# mcu.net
KiCad netlist of a schematic drawn in Altium Designer
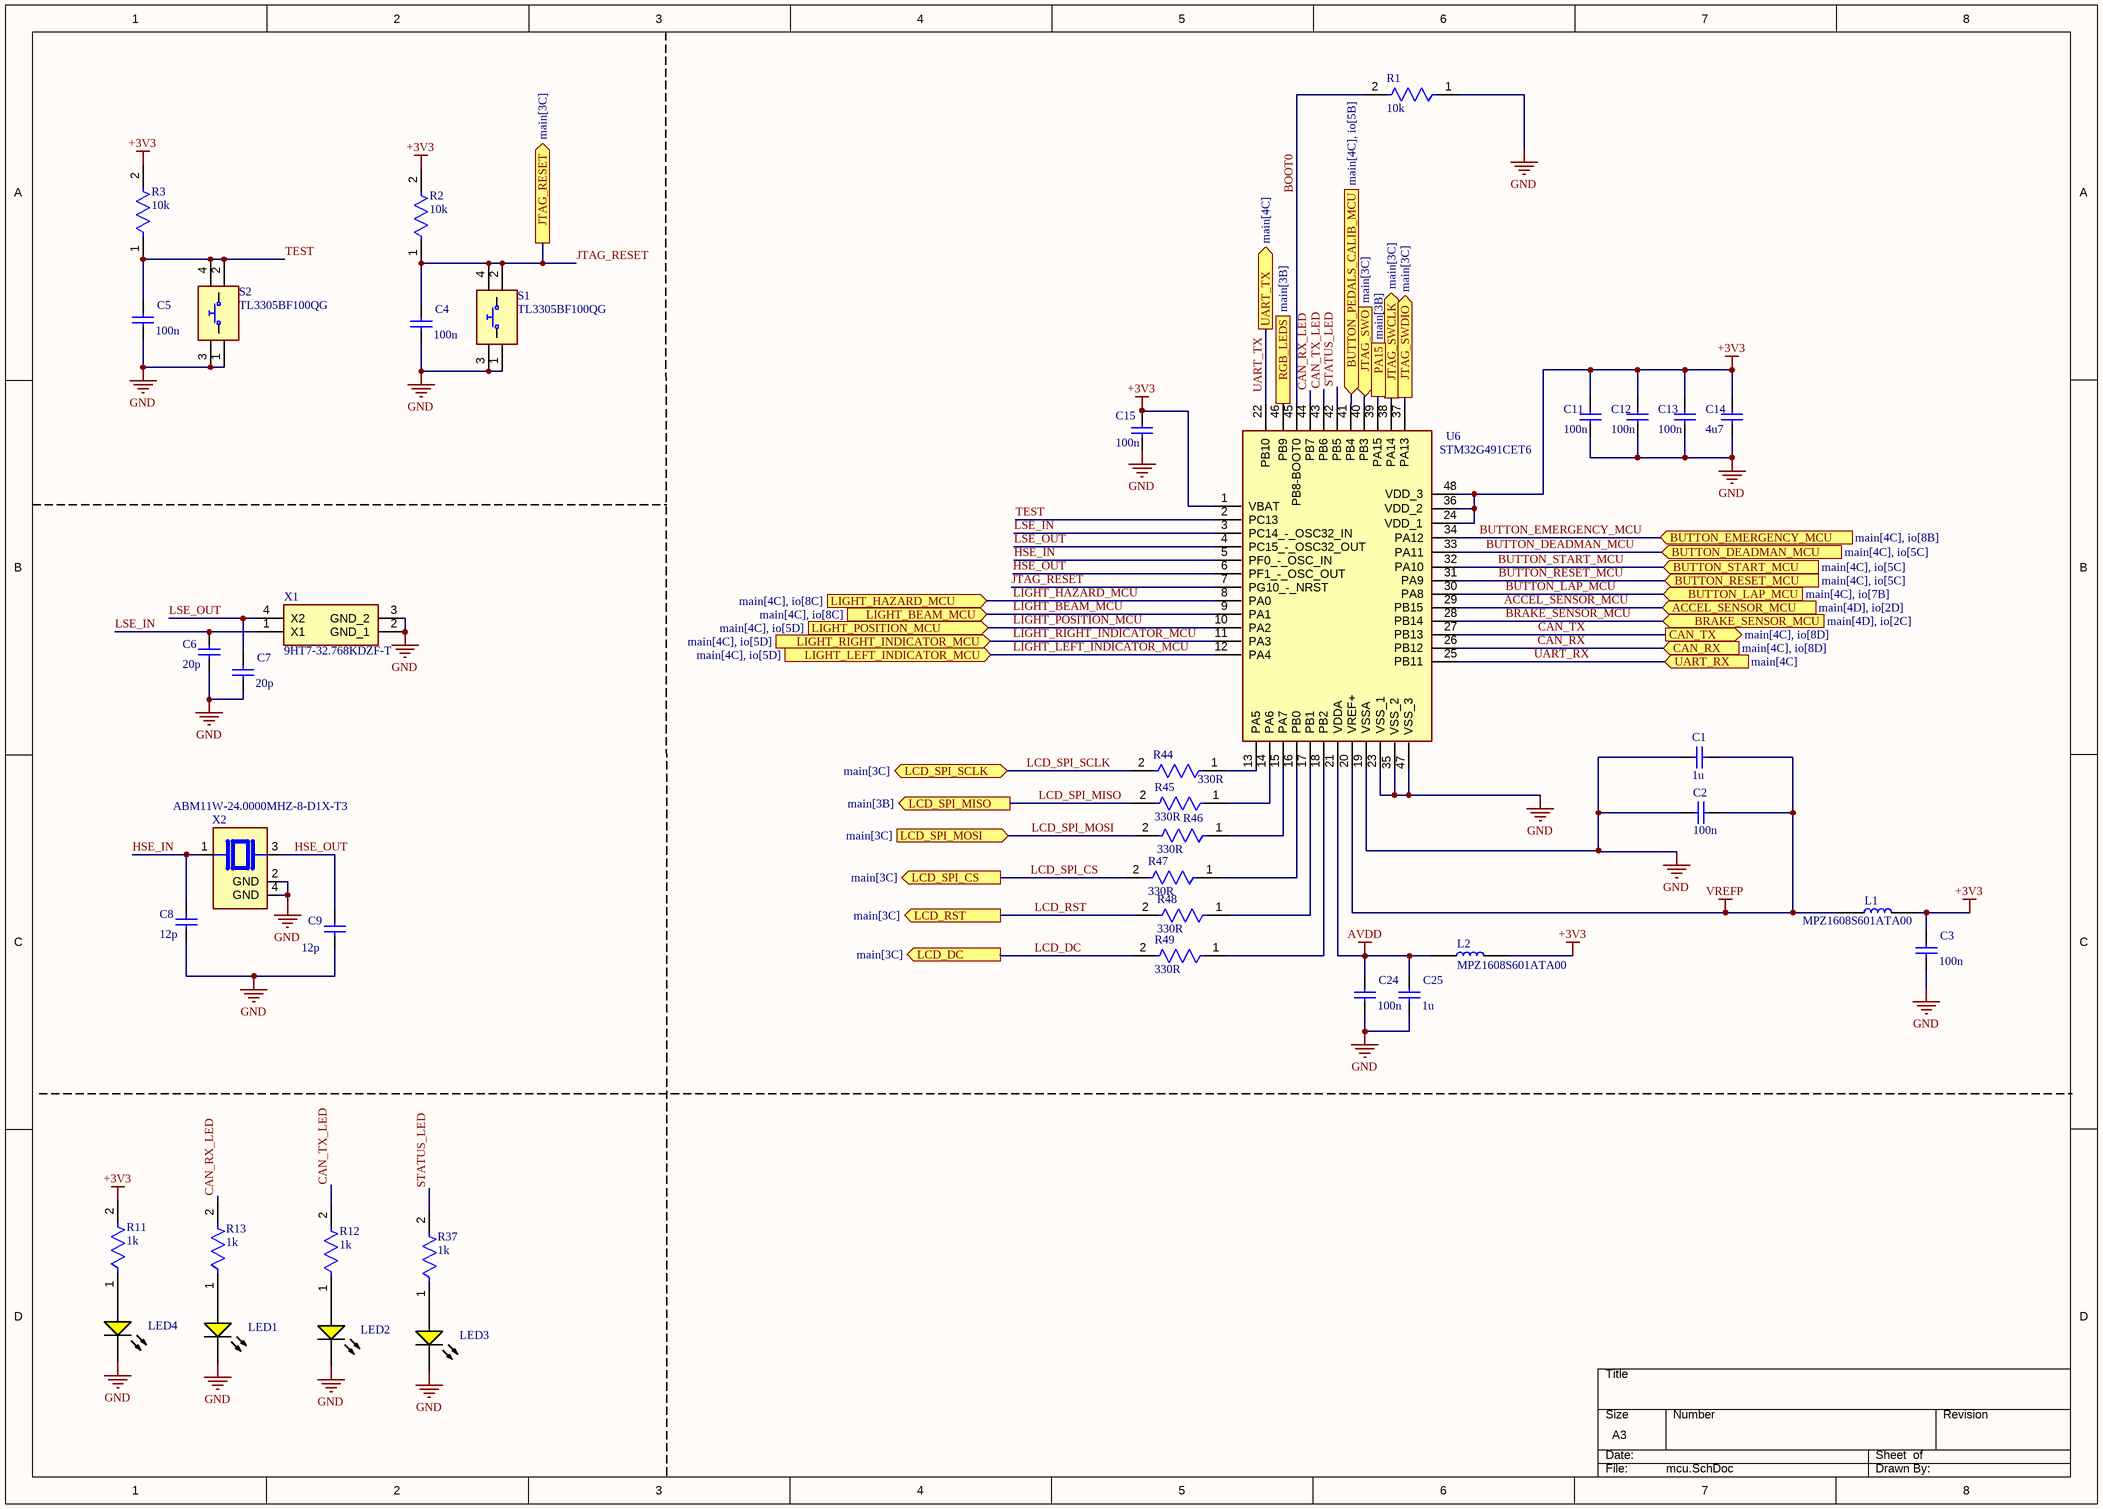
[diagram p0: mcu.SchDoc]

(export (version "E")
  (design (tool "Eeschema 10.0.6"))
  (components
    (comp (ref "C1")
      (value "1u")
      (footprint "CAPC1206(3216)150_L")
      (description "CAP 1.8uF 10V ±5% 1206 (3216 Metric) Thickness 1.45mm SMD")
      (fields (field (name "TOLERANCE") "Â±5%"))
      (libsource (lib "Altium Content Vault") (part "CAP"))
    )
    (comp (ref "C2")
      (value "100n")
      (footprint "CAPC1206(3216)150_L")
      (description "CAP 1.8uF 10V ±5% 1206 (3216 Metric) Thickness 1.45mm SMD")
      (fields (field (name "TOLERANCE") "Â±5%"))
      (libsource (lib "Altium Content Vault") (part "CAP"))
    )
    (comp (ref "C3")
      (value "100n")
      (footprint "CAPC1206(3216)150_L")
      (description "CAP 1.8uF 10V ±5% 1206 (3216 Metric) Thickness 1.45mm SMD")
      (fields (field (name "TOLERANCE") "Â±5%"))
      (libsource (lib "Altium Content Vault") (part "CAP"))
    )
    (comp (ref "C4")
      (value "100n")
      (footprint "CAPC1206(3216)150_L")
      (description "CAP 1.8uF 10V ±5% 1206 (3216 Metric) Thickness 1.45mm SMD")
      (fields (field (name "TOLERANCE") "Â±5%"))
      (libsource (lib "Altium Content Vault") (part "CAP"))
    )
    (comp (ref "C5")
      (value "100n")
      (footprint "CAPC1206(3216)150_L")
      (description "CAP 1.8uF 10V ±5% 1206 (3216 Metric) Thickness 1.45mm SMD")
      (fields (field (name "TOLERANCE") "Â±5%"))
      (libsource (lib "Altium Content Vault") (part "CAP"))
    )
    (comp (ref "C6")
      (value "20p")
      (footprint "CAPC1206(3216)150_L")
      (description "CAP 1.8uF 10V ±5% 1206 (3216 Metric) Thickness 1.45mm SMD")
      (fields (field (name "TOLERANCE") "Â±5%"))
      (libsource (lib "Altium Content Vault") (part "CAP"))
    )
    (comp (ref "C7")
      (value "20p")
      (footprint "CAPC1206(3216)150_L")
      (description "CAP 1.8uF 10V ±5% 1206 (3216 Metric) Thickness 1.45mm SMD")
      (fields (field (name "TOLERANCE") "Â±5%"))
      (libsource (lib "Altium Content Vault") (part "CAP"))
    )
    (comp (ref "C8")
      (value "12p")
      (footprint "CAPC1206(3216)150_L")
      (description "CAP 1.8uF 10V ±5% 1206 (3216 Metric) Thickness 1.45mm SMD")
      (fields (field (name "TOLERANCE") "Â±5%"))
      (libsource (lib "Altium Content Vault") (part "CAP"))
    )
    (comp (ref "C9")
      (value "12p")
      (footprint "CAPC1206(3216)150_L")
      (description "CAP 1.8uF 10V ±5% 1206 (3216 Metric) Thickness 1.45mm SMD")
      (fields (field (name "TOLERANCE") "Â±5%"))
      (libsource (lib "Altium Content Vault") (part "CAP"))
    )
    (comp (ref "C11")
      (value "100n")
      (footprint "CAPC1206(3216)150_L")
      (description "CAP 1.8uF 10V ±5% 1206 (3216 Metric) Thickness 1.45mm SMD")
      (fields (field (name "TOLERANCE") "Â±5%"))
      (libsource (lib "Altium Content Vault") (part "CAP"))
    )
    (comp (ref "C12")
      (value "100n")
      (footprint "CAPC1206(3216)150_L")
      (description "CAP 1.8uF 10V ±5% 1206 (3216 Metric) Thickness 1.45mm SMD")
      (fields (field (name "TOLERANCE") "Â±5%"))
      (libsource (lib "Altium Content Vault") (part "CAP"))
    )
    (comp (ref "C13")
      (value "100n")
      (footprint "CAPC1206(3216)150_L")
      (description "CAP 1.8uF 10V ±5% 1206 (3216 Metric) Thickness 1.45mm SMD")
      (fields (field (name "TOLERANCE") "Â±5%"))
      (libsource (lib "Altium Content Vault") (part "CAP"))
    )
    (comp (ref "C14")
      (value "4u7")
      (footprint "CAPC1206(3216)150_L")
      (description "CAP 1.8uF 10V ±5% 1206 (3216 Metric) Thickness 1.45mm SMD")
      (fields (field (name "TOLERANCE") "Â±5%"))
      (libsource (lib "Altium Content Vault") (part "CAP"))
    )
    (comp (ref "C15")
      (value "100n")
      (footprint "CAPC1206(3216)150_L")
      (description "CAP 1.8uF 10V ±5% 1206 (3216 Metric) Thickness 1.45mm SMD")
      (fields (field (name "TOLERANCE") "Â±5%"))
      (libsource (lib "Altium Content Vault") (part "CAP"))
    )
    (comp (ref "C24")
      (value "100n")
      (footprint "CAPC1206(3216)150_L")
      (description "CAP 1.8uF 10V ±5% 1206 (3216 Metric) Thickness 1.45mm SMD")
      (fields (field (name "TOLERANCE") "Â±5%"))
      (libsource (lib "Altium Content Vault") (part "CAP"))
    )
    (comp (ref "C25")
      (value "1u")
      (footprint "CAPC1206(3216)150_L")
      (description "CAP 1.8uF 10V ±5% 1206 (3216 Metric) Thickness 1.45mm SMD")
      (fields (field (name "TOLERANCE") "Â±5%"))
      (libsource (lib "Altium Content Vault") (part "CAP"))
    )
    (comp (ref "L1")
      (value "MPZ1608S601ATA00")
      (footprint "INDC1608X95N")
      (description "Ferrite Beads Multi-Layer 600Ohm 25% 100MHz 1A 0.15Ohm DCR 0603 T/R")
      (fields (field (name "MF") "TDK") (field (name "TOLERANCE") "25%"))
      (libsource (lib "HydrogreenLibrary") (part "MPZ1608S601ATA00"))
    )
    (comp (ref "L2")
      (value "MPZ1608S601ATA00")
      (footprint "INDC1608X95N")
      (description "Ferrite Beads Multi-Layer 600Ohm 25% 100MHz 1A 0.15Ohm DCR 0603 T/R")
      (fields (field (name "MF") "TDK") (field (name "TOLERANCE") "25%"))
      (libsource (lib "HydrogreenLibrary") (part "MPZ1608S601ATA00"))
    )
    (comp (ref "LED1")
      (value "~")
      (footprint "LUMX-SML-LX1206YC-TR_V")
      (description "Yellow LED, Water Clear Len, 585 nm, 2.1 V, -40 to 85 degC, 2-Pin SMD, RoHS, Tape and Reel")
      (fields (field (name "MANUFACTURER") "Lumex"))
      (libsource (lib "Altium Content Vault") (part "LED-YELLOW-AK-2"))
    )
    (comp (ref "LED2")
      (value "~")
      (footprint "LUMX-SML-LX1206YC-TR_V")
      (description "Yellow LED, Water Clear Len, 585 nm, 2.1 V, -40 to 85 degC, 2-Pin SMD, RoHS, Tape and Reel")
      (fields (field (name "MANUFACTURER") "Lumex"))
      (libsource (lib "Altium Content Vault") (part "LED-YELLOW-AK-2"))
    )
    (comp (ref "LED3")
      (value "~")
      (footprint "LUMX-SML-LX1206YC-TR_V")
      (description "Yellow LED, Water Clear Len, 585 nm, 2.1 V, -40 to 85 degC, 2-Pin SMD, RoHS, Tape and Reel")
      (fields (field (name "MANUFACTURER") "Lumex"))
      (libsource (lib "Altium Content Vault") (part "LED-YELLOW-AK-2"))
    )
    (comp (ref "LED4")
      (value "~")
      (footprint "LUMX-SML-LX1206YC-TR_V")
      (description "Yellow LED, Water Clear Len, 585 nm, 2.1 V, -40 to 85 degC, 2-Pin SMD, RoHS, Tape and Reel")
      (fields (field (name "MANUFACTURER") "Lumex"))
      (libsource (lib "Altium Content Vault") (part "LED-YELLOW-AK-2"))
    )
    (comp (ref "R1")
      (value "10k")
      (footprint "FP-RK73H2B-MFG")
      (description "40.2kΩ ±1% 0.25W Chip Resistor 1206 Thick Film AEC-Q200 Qualified")
      (fields (field (name "TOLERANCE") "1%"))
      (libsource (lib "Altium Content Vault") (part "1029c3af85768c4190bb7ad29bc67b5"))
    )
    (comp (ref "R2")
      (value "10k")
      (footprint "FP-RK73H2B-MFG")
      (description "40.2kΩ ±1% 0.25W Chip Resistor 1206 Thick Film AEC-Q200 Qualified")
      (fields (field (name "TOLERANCE") "1%"))
      (libsource (lib "Altium Content Vault") (part "1029c3af85768c4190bb7ad29bc67b5"))
    )
    (comp (ref "R3")
      (value "10k")
      (footprint "FP-RK73H2B-MFG")
      (description "40.2kΩ ±1% 0.25W Chip Resistor 1206 Thick Film AEC-Q200 Qualified")
      (fields (field (name "TOLERANCE") "1%"))
      (libsource (lib "Altium Content Vault") (part "1029c3af85768c4190bb7ad29bc67b5"))
    )
    (comp (ref "R11")
      (value "1k")
      (footprint "FP-RK73H2B-MFG")
      (description "40.2kΩ ±1% 0.25W Chip Resistor 1206 Thick Film AEC-Q200 Qualified")
      (fields (field (name "TOLERANCE") "1%"))
      (libsource (lib "Altium Content Vault") (part "1029c3af85768c4190bb7ad29bc67b5"))
    )
    (comp (ref "R12")
      (value "1k")
      (footprint "FP-RK73H2B-MFG")
      (description "40.2kΩ ±1% 0.25W Chip Resistor 1206 Thick Film AEC-Q200 Qualified")
      (fields (field (name "TOLERANCE") "1%"))
      (libsource (lib "Altium Content Vault") (part "1029c3af85768c4190bb7ad29bc67b5"))
    )
    (comp (ref "R13")
      (value "1k")
      (footprint "FP-RK73H2B-MFG")
      (description "40.2kΩ ±1% 0.25W Chip Resistor 1206 Thick Film AEC-Q200 Qualified")
      (fields (field (name "TOLERANCE") "1%"))
      (libsource (lib "Altium Content Vault") (part "1029c3af85768c4190bb7ad29bc67b5"))
    )
    (comp (ref "R37")
      (value "1k")
      (footprint "FP-RK73H2B-MFG")
      (description "40.2kΩ ±1% 0.25W Chip Resistor 1206 Thick Film AEC-Q200 Qualified")
      (fields (field (name "TOLERANCE") "1%"))
      (libsource (lib "Altium Content Vault") (part "1029c3af85768c4190bb7ad29bc67b5"))
    )
    (comp (ref "R44")
      (value "330R")
      (footprint "FP-RK73H2B-MFG")
      (description "40.2kΩ ±1% 0.25W Chip Resistor 1206 Thick Film AEC-Q200 Qualified")
      (fields (field (name "TOLERANCE") "1%"))
      (libsource (lib "Altium Content Vault") (part "1029c3af85768c4190bb7ad29bc67b5"))
    )
    (comp (ref "R45")
      (value "330R")
      (footprint "FP-RK73H2B-MFG")
      (description "40.2kΩ ±1% 0.25W Chip Resistor 1206 Thick Film AEC-Q200 Qualified")
      (fields (field (name "TOLERANCE") "1%"))
      (libsource (lib "Altium Content Vault") (part "1029c3af85768c4190bb7ad29bc67b5"))
    )
    (comp (ref "R46")
      (value "330R")
      (footprint "FP-RK73H2B-MFG")
      (description "40.2kΩ ±1% 0.25W Chip Resistor 1206 Thick Film AEC-Q200 Qualified")
      (fields (field (name "TOLERANCE") "1%"))
      (libsource (lib "Altium Content Vault") (part "1029c3af85768c4190bb7ad29bc67b5"))
    )
    (comp (ref "R47")
      (value "330R")
      (footprint "FP-RK73H2B-MFG")
      (description "40.2kΩ ±1% 0.25W Chip Resistor 1206 Thick Film AEC-Q200 Qualified")
      (fields (field (name "TOLERANCE") "1%"))
      (libsource (lib "Altium Content Vault") (part "1029c3af85768c4190bb7ad29bc67b5"))
    )
    (comp (ref "R48")
      (value "330R")
      (footprint "FP-RK73H2B-MFG")
      (description "40.2kΩ ±1% 0.25W Chip Resistor 1206 Thick Film AEC-Q200 Qualified")
      (fields (field (name "TOLERANCE") "1%"))
      (libsource (lib "Altium Content Vault") (part "1029c3af85768c4190bb7ad29bc67b5"))
    )
    (comp (ref "R49")
      (value "330R")
      (footprint "FP-RK73H2B-MFG")
      (description "40.2kΩ ±1% 0.25W Chip Resistor 1206 Thick Film AEC-Q200 Qualified")
      (fields (field (name "TOLERANCE") "1%"))
      (libsource (lib "Altium Content Vault") (part "1029c3af85768c4190bb7ad29bc67b5"))
    )
    (comp (ref "S1")
      (value "TL3305BF100QG")
      (footprint "TL3305BF160QG")
      (description "TL3305 Ultra-Miniature Tact Switch 100gf 5.0mm actuator Silver Contact Gullwing")
      (fields
        (field (name "MOUSER PART NUMBER") "612-TL3305BF100QG")
        (field (name "MANUFACTURER") "E-Switch")
      )
      (libsource (lib "HydrogreenLibrary") (part "TL3305BF100QG"))
    )
    (comp (ref "S2")
      (value "TL3305BF100QG")
      (footprint "TL3305BF160QG")
      (description "TL3305 Ultra-Miniature Tact Switch 100gf 5.0mm actuator Silver Contact Gullwing")
      (fields
        (field (name "MOUSER PART NUMBER") "612-TL3305BF100QG")
        (field (name "MANUFACTURER") "E-Switch")
      )
      (libsource (lib "HydrogreenLibrary") (part "TL3305BF100QG"))
    )
    (comp (ref "U6")
      (value "STM32G491CET6")
      (footprint "STM32G491CET6")
      (description "ARM Microcontrollers - MCU Mainstream Arm Cortex-M4+ MCU 170MHz with 512Kbytes of Flash memory")
      (fields (field (name "MOUSER PART NUMBER") "511-STM32G491CET6"))
      (libsource (lib "HydrogreenLibrary") (part "STM32G491CET6"))
    )
    (comp (ref "X1")
      (value "9HT7-32.768KDZF-T")
      (footprint "9HT732768KDZFT")
      (description "Parallel - Fundamental Quartz Crystal, 0.032768MHz Nom")
      (fields (field (name "MOUSER PART NUMBER") "717-9HT7-32.768KDZFT") (field (name "MANUFACTURER") "TXC"))
      (libsource (lib "HydrogreenLibrary") (part "9HT7-32.768KDZF-T"))
    )
    (comp (ref "X2")
      (value "ABM11W-24.0000MHZ-8-D1X-T3")
      (footprint "XTAL_ABM11W-24.0000MHZ-8-D1X-T3")
      (description "Crystal, Quartz, 24 MHz, SMD, 2mm x 1.6mm x 0.5mm, 20 ppm, 8 pF, 10 ppm, ABM11W")
      (fields (field (name "MF") "Abracon LLC") (field (name "MANUFACTURER") "Abracon"))
      (libsource (lib "HydrogreenLibrary") (part "ABM11W-24.0000MHZ-8-D1X-T3"))
    )
  )
  (nets
    (net (code "1") (name "+3V3") (class "Default")
      (node (ref "C11") (pin "1") (pinfunction "1_1") (pintype "passive"))
      (node (ref "C12") (pin "1") (pinfunction "1_1") (pintype "passive"))
      (node (ref "C13") (pin "1") (pinfunction "1_1") (pintype "passive"))
      (node (ref "C14") (pin "1") (pinfunction "1_1") (pintype "passive"))
      (node (ref "C15") (pin "1") (pinfunction "1_1") (pintype "passive"))
      (node (ref "C3") (pin "1") (pinfunction "1_1") (pintype "passive"))
      (node (ref "L1") (pin "2") (pinfunction "2_2") (pintype "passive"))
      (node (ref "L2") (pin "2") (pinfunction "2_2") (pintype "passive"))
      (node (ref "R11") (pin "2") (pinfunction "2_2") (pintype "passive"))
      (node (ref "R2") (pin "2") (pinfunction "2_2") (pintype "passive"))
      (node (ref "R3") (pin "2") (pinfunction "2_2") (pintype "passive"))
      (node (ref "U6") (pin "1") (pinfunction "VBAT_1") (pintype "passive"))
      (node (ref "U6") (pin "24") (pinfunction "VDD_1_24") (pintype "passive"))
      (node (ref "U6") (pin "36") (pinfunction "VDD_2_36") (pintype "passive"))
      (node (ref "U6") (pin "48") (pinfunction "VDD_3_48") (pintype "passive"))
    )
    (net (code "2") (name "/ACCEL_SENSOR_MCU") (class "Default")
      (node (ref "U6") (pin "29") (pinfunction "PB15_29") (pintype "passive"))
    )
    (net (code "3") (name "/BOOT0") (class "Default")
      (node (ref "R1") (pin "2") (pinfunction "2_2") (pintype "passive"))
      (node (ref "U6") (pin "45") (pinfunction "PB8-BOOT0_45") (pintype "passive"))
    )
    (net (code "4") (name "/BRAKE_SENSOR_MCU") (class "Default")
      (node (ref "U6") (pin "28") (pinfunction "PB14_28") (pintype "passive"))
    )
    (net (code "5") (name "/BUTTON_DEADMAN_MCU") (class "Default")
      (node (ref "U6") (pin "33") (pinfunction "PA11_33") (pintype "passive"))
    )
    (net (code "6") (name "/BUTTON_EMERGENCY_MCU") (class "Default")
      (node (ref "U6") (pin "34") (pinfunction "PA12_34") (pintype "passive"))
    )
    (net (code "7") (name "/BUTTON_LAP_MCU") (class "Default")
      (node (ref "U6") (pin "30") (pinfunction "PA8_30") (pintype "passive"))
    )
    (net (code "8") (name "/BUTTON_PEDALS_CALIB_MCU") (class "Default")
      (node (ref "U6") (pin "41") (pinfunction "PB4_41") (pintype "passive"))
    )
    (net (code "9") (name "/BUTTON_RESET_MCU") (class "Default")
      (node (ref "U6") (pin "31") (pinfunction "PA9_31") (pintype "passive"))
    )
    (net (code "10") (name "/BUTTON_START_MCU") (class "Default")
      (node (ref "U6") (pin "32") (pinfunction "PA10_32") (pintype "passive"))
    )
    (net (code "11") (name "/CAN_RX") (class "Default")
      (node (ref "U6") (pin "26") (pinfunction "PB12_26") (pintype "passive"))
    )
    (net (code "12") (name "/CAN_RX_LED") (class "Default")
      (node (ref "R13") (pin "2") (pinfunction "2_2") (pintype "passive"))
      (node (ref "U6") (pin "44") (pinfunction "PB7_44") (pintype "passive"))
    )
    (net (code "13") (name "/CAN_TX") (class "Default")
      (node (ref "U6") (pin "27") (pinfunction "PB13_27") (pintype "passive"))
    )
    (net (code "14") (name "/CAN_TX_LED") (class "Default")
      (node (ref "R12") (pin "2") (pinfunction "2_2") (pintype "passive"))
      (node (ref "U6") (pin "43") (pinfunction "PB6_43") (pintype "passive"))
    )
    (net (code "15") (name "/HSE_IN") (class "Default")
      (node (ref "C8") (pin "1") (pinfunction "1_1") (pintype "passive"))
      (node (ref "U6") (pin "5") (pinfunction "PF0_-_OSC_IN_5") (pintype "passive"))
      (node (ref "X2") (pin "1") (pinfunction "1_1") (pintype "passive"))
    )
    (net (code "16") (name "/HSE_OUT") (class "Default")
      (node (ref "C9") (pin "1") (pinfunction "1_1") (pintype "passive"))
      (node (ref "U6") (pin "6") (pinfunction "PF1_-_OSC_OUT_6") (pintype "passive"))
      (node (ref "X2") (pin "3") (pinfunction "2_3") (pintype "passive"))
    )
    (net (code "17") (name "/JTAG_RESET") (class "Default")
      (node (ref "C4") (pin "1") (pinfunction "1_1") (pintype "passive"))
      (node (ref "R2") (pin "1") (pinfunction "1_1") (pintype "passive"))
      (node (ref "S1") (pin "2") (pintype "passive"))
      (node (ref "S1") (pin "4") (pintype "passive"))
      (node (ref "U6") (pin "7") (pinfunction "PG10_-_NRST_7") (pintype "passive"))
    )
    (net (code "18") (name "/JTAG_SWCLK") (class "Default")
      (node (ref "U6") (pin "38") (pinfunction "PA14_38") (pintype "passive"))
    )
    (net (code "19") (name "/JTAG_SWDIO") (class "Default")
      (node (ref "U6") (pin "37") (pinfunction "PA13_37") (pintype "passive"))
    )
    (net (code "20") (name "/JTAG_SWO") (class "Default")
      (node (ref "U6") (pin "40") (pinfunction "PB3_40") (pintype "passive"))
    )
    (net (code "21") (name "/LCD_DC") (class "Default")
      (node (ref "R49") (pin "2") (pinfunction "2_2") (pintype "passive"))
    )
    (net (code "22") (name "/LCD_RST") (class "Default")
      (node (ref "R48") (pin "2") (pinfunction "2_2") (pintype "passive"))
    )
    (net (code "23") (name "/LCD_SPI_CS") (class "Default")
      (node (ref "R47") (pin "2") (pinfunction "2_2") (pintype "passive"))
    )
    (net (code "24") (name "/LCD_SPI_MISO") (class "Default")
      (node (ref "R45") (pin "2") (pinfunction "2_2") (pintype "passive"))
    )
    (net (code "25") (name "/LCD_SPI_MOSI") (class "Default")
      (node (ref "R46") (pin "2") (pinfunction "2_2") (pintype "passive"))
    )
    (net (code "26") (name "/LCD_SPI_SCLK") (class "Default")
      (node (ref "R44") (pin "2") (pinfunction "2_2") (pintype "passive"))
    )
    (net (code "27") (name "/LIGHT_BEAM_MCU") (class "Default")
      (node (ref "U6") (pin "9") (pinfunction "PA1_9") (pintype "passive"))
    )
    (net (code "28") (name "/LIGHT_HAZARD_MCU") (class "Default")
      (node (ref "U6") (pin "8") (pinfunction "PA0_8") (pintype "passive"))
    )
    (net (code "29") (name "/LIGHT_LEFT_INDICATOR_MCU") (class "Default")
      (node (ref "U6") (pin "12") (pinfunction "PA4_12") (pintype "passive"))
    )
    (net (code "30") (name "/LIGHT_POSITION_MCU") (class "Default")
      (node (ref "U6") (pin "10") (pinfunction "PA2_10") (pintype "passive"))
    )
    (net (code "31") (name "/LIGHT_RIGHT_INDICATOR_MCU") (class "Default")
      (node (ref "U6") (pin "11") (pinfunction "PA3_11") (pintype "passive"))
    )
    (net (code "32") (name "/LSE_IN") (class "Default")
      (node (ref "C6") (pin "1") (pinfunction "1_1") (pintype "passive"))
      (node (ref "U6") (pin "3") (pinfunction "PC14_-_OSC32_IN_3") (pintype "passive"))
      (node (ref "X1") (pin "1") (pinfunction "X1_1") (pintype "passive"))
    )
    (net (code "33") (name "/LSE_OUT") (class "Default")
      (node (ref "C7") (pin "1") (pinfunction "1_1") (pintype "passive"))
      (node (ref "U6") (pin "4") (pinfunction "PC15_-_OSC32_OUT_4") (pintype "passive"))
      (node (ref "X1") (pin "4") (pinfunction "X2_4") (pintype "passive"))
    )
    (net (code "34") (name "/PA15") (class "Default")
      (node (ref "U6") (pin "39") (pinfunction "PA15_39") (pintype "passive"))
    )
    (net (code "35") (name "/RGB_LEDS") (class "Default")
      (node (ref "U6") (pin "46") (pinfunction "PB9_46") (pintype "passive"))
    )
    (net (code "36") (name "/STATUS_LED") (class "Default")
      (node (ref "R37") (pin "2") (pinfunction "2_2") (pintype "passive"))
      (node (ref "U6") (pin "42") (pinfunction "PB5_42") (pintype "passive"))
    )
    (net (code "37") (name "/TEST") (class "Default")
      (node (ref "C5") (pin "1") (pinfunction "1_1") (pintype "passive"))
      (node (ref "R3") (pin "1") (pinfunction "1_1") (pintype "passive"))
      (node (ref "S2") (pin "2") (pintype "passive"))
      (node (ref "S2") (pin "4") (pintype "passive"))
      (node (ref "U6") (pin "2") (pinfunction "PC13_2") (pintype "passive"))
    )
    (net (code "38") (name "/UART_RX") (class "Default")
      (node (ref "U6") (pin "25") (pinfunction "PB11_25") (pintype "passive"))
    )
    (net (code "39") (name "/UART_TX") (class "Default")
      (node (ref "U6") (pin "22") (pinfunction "PB10_22") (pintype "passive"))
    )
    (net (code "40") (name "AVDD") (class "Default")
      (node (ref "C24") (pin "1") (pinfunction "1_1") (pintype "passive"))
      (node (ref "C25") (pin "1") (pinfunction "1_1") (pintype "passive"))
      (node (ref "L2") (pin "1") (pinfunction "1_1") (pintype "passive"))
      (node (ref "U6") (pin "21") (pinfunction "VDDA_21") (pintype "passive"))
    )
    (net (code "41") (name "GND") (class "Default")
      (node (ref "C1") (pin "1") (pinfunction "1_1") (pintype "passive"))
      (node (ref "C11") (pin "2") (pinfunction "2_2") (pintype "passive"))
      (node (ref "C12") (pin "2") (pinfunction "2_2") (pintype "passive"))
      (node (ref "C13") (pin "2") (pinfunction "2_2") (pintype "passive"))
      (node (ref "C14") (pin "2") (pinfunction "2_2") (pintype "passive"))
      (node (ref "C15") (pin "2") (pinfunction "2_2") (pintype "passive"))
      (node (ref "C2") (pin "1") (pinfunction "1_1") (pintype "passive"))
      (node (ref "C24") (pin "2") (pinfunction "2_2") (pintype "passive"))
      (node (ref "C25") (pin "2") (pinfunction "2_2") (pintype "passive"))
      (node (ref "C3") (pin "2") (pinfunction "2_2") (pintype "passive"))
      (node (ref "C4") (pin "2") (pinfunction "2_2") (pintype "passive"))
      (node (ref "C5") (pin "2") (pinfunction "2_2") (pintype "passive"))
      (node (ref "C6") (pin "2") (pinfunction "2_2") (pintype "passive"))
      (node (ref "C7") (pin "2") (pinfunction "2_2") (pintype "passive"))
      (node (ref "C8") (pin "2") (pinfunction "2_2") (pintype "passive"))
      (node (ref "C9") (pin "2") (pinfunction "2_2") (pintype "passive"))
      (node (ref "LED1") (pin "2") (pinfunction "K_2") (pintype "passive"))
      (node (ref "LED2") (pin "2") (pinfunction "K_2") (pintype "passive"))
      (node (ref "LED3") (pin "2") (pinfunction "K_2") (pintype "passive"))
      (node (ref "LED4") (pin "2") (pinfunction "K_2") (pintype "passive"))
      (node (ref "R1") (pin "1") (pinfunction "1_1") (pintype "passive"))
      (node (ref "S1") (pin "1") (pintype "passive"))
      (node (ref "S1") (pin "3") (pintype "passive"))
      (node (ref "S2") (pin "1") (pintype "passive"))
      (node (ref "S2") (pin "3") (pintype "passive"))
      (node (ref "U6") (pin "19") (pinfunction "VSSA_19") (pintype "passive"))
      (node (ref "U6") (pin "23") (pinfunction "VSS_1_23") (pintype "passive"))
      (node (ref "U6") (pin "35") (pinfunction "VSS_2_35") (pintype "passive"))
      (node (ref "U6") (pin "47") (pinfunction "VSS_3_47") (pintype "passive"))
      (node (ref "X1") (pin "2") (pinfunction "GND_1_2") (pintype "passive"))
      (node (ref "X1") (pin "3") (pinfunction "GND_2_3") (pintype "passive"))
      (node (ref "X2") (pin "2") (pinfunction "GND_2") (pintype "power_in"))
      (node (ref "X2") (pin "4") (pinfunction "GND_4") (pintype "power_in"))
    )
    (net (code "42") (name "Net-(LED1-A)") (class "Default")
      (node (ref "LED1") (pin "1") (pinfunction "A_1") (pintype "passive"))
      (node (ref "R13") (pin "1") (pinfunction "1_1") (pintype "passive"))
    )
    (net (code "43") (name "Net-(LED2-A)") (class "Default")
      (node (ref "LED2") (pin "1") (pinfunction "A_1") (pintype "passive"))
      (node (ref "R12") (pin "1") (pinfunction "1_1") (pintype "passive"))
    )
    (net (code "44") (name "Net-(LED3-A)") (class "Default")
      (node (ref "LED3") (pin "1") (pinfunction "A_1") (pintype "passive"))
      (node (ref "R37") (pin "1") (pinfunction "1_1") (pintype "passive"))
    )
    (net (code "45") (name "Net-(LED4-A)") (class "Default")
      (node (ref "LED4") (pin "1") (pinfunction "A_1") (pintype "passive"))
      (node (ref "R11") (pin "1") (pinfunction "1_1") (pintype "passive"))
    )
    (net (code "46") (name "Net-(U6-PA5)") (class "Default")
      (node (ref "R44") (pin "1") (pinfunction "1_1") (pintype "passive"))
      (node (ref "U6") (pin "13") (pinfunction "PA5_13") (pintype "passive"))
    )
    (net (code "47") (name "Net-(U6-PA6)") (class "Default")
      (node (ref "R45") (pin "1") (pinfunction "1_1") (pintype "passive"))
      (node (ref "U6") (pin "14") (pinfunction "PA6_14") (pintype "passive"))
    )
    (net (code "48") (name "Net-(U6-PA7)") (class "Default")
      (node (ref "R46") (pin "1") (pinfunction "1_1") (pintype "passive"))
      (node (ref "U6") (pin "15") (pinfunction "PA7_15") (pintype "passive"))
    )
    (net (code "49") (name "Net-(U6-PB0)") (class "Default")
      (node (ref "R47") (pin "1") (pinfunction "1_1") (pintype "passive"))
      (node (ref "U6") (pin "16") (pinfunction "PB0_16") (pintype "passive"))
    )
    (net (code "50") (name "Net-(U6-PB1)") (class "Default")
      (node (ref "R48") (pin "1") (pinfunction "1_1") (pintype "passive"))
      (node (ref "U6") (pin "17") (pinfunction "PB1_17") (pintype "passive"))
    )
    (net (code "51") (name "Net-(U6-PB2)") (class "Default")
      (node (ref "R49") (pin "1") (pinfunction "1_1") (pintype "passive"))
      (node (ref "U6") (pin "18") (pinfunction "PB2_18") (pintype "passive"))
    )
    (net (code "52") (name "VREFP") (class "Default")
      (node (ref "C1") (pin "2") (pinfunction "2_2") (pintype "passive"))
      (node (ref "C2") (pin "2") (pinfunction "2_2") (pintype "passive"))
      (node (ref "L1") (pin "1") (pinfunction "1_1") (pintype "passive"))
      (node (ref "U6") (pin "20") (pinfunction "VREF+_20") (pintype "passive"))
    )
  )
)
